# 12F1840_Controller_2020_03_04_A.net
KiCad netlist of a schematic drawn in EAGLE
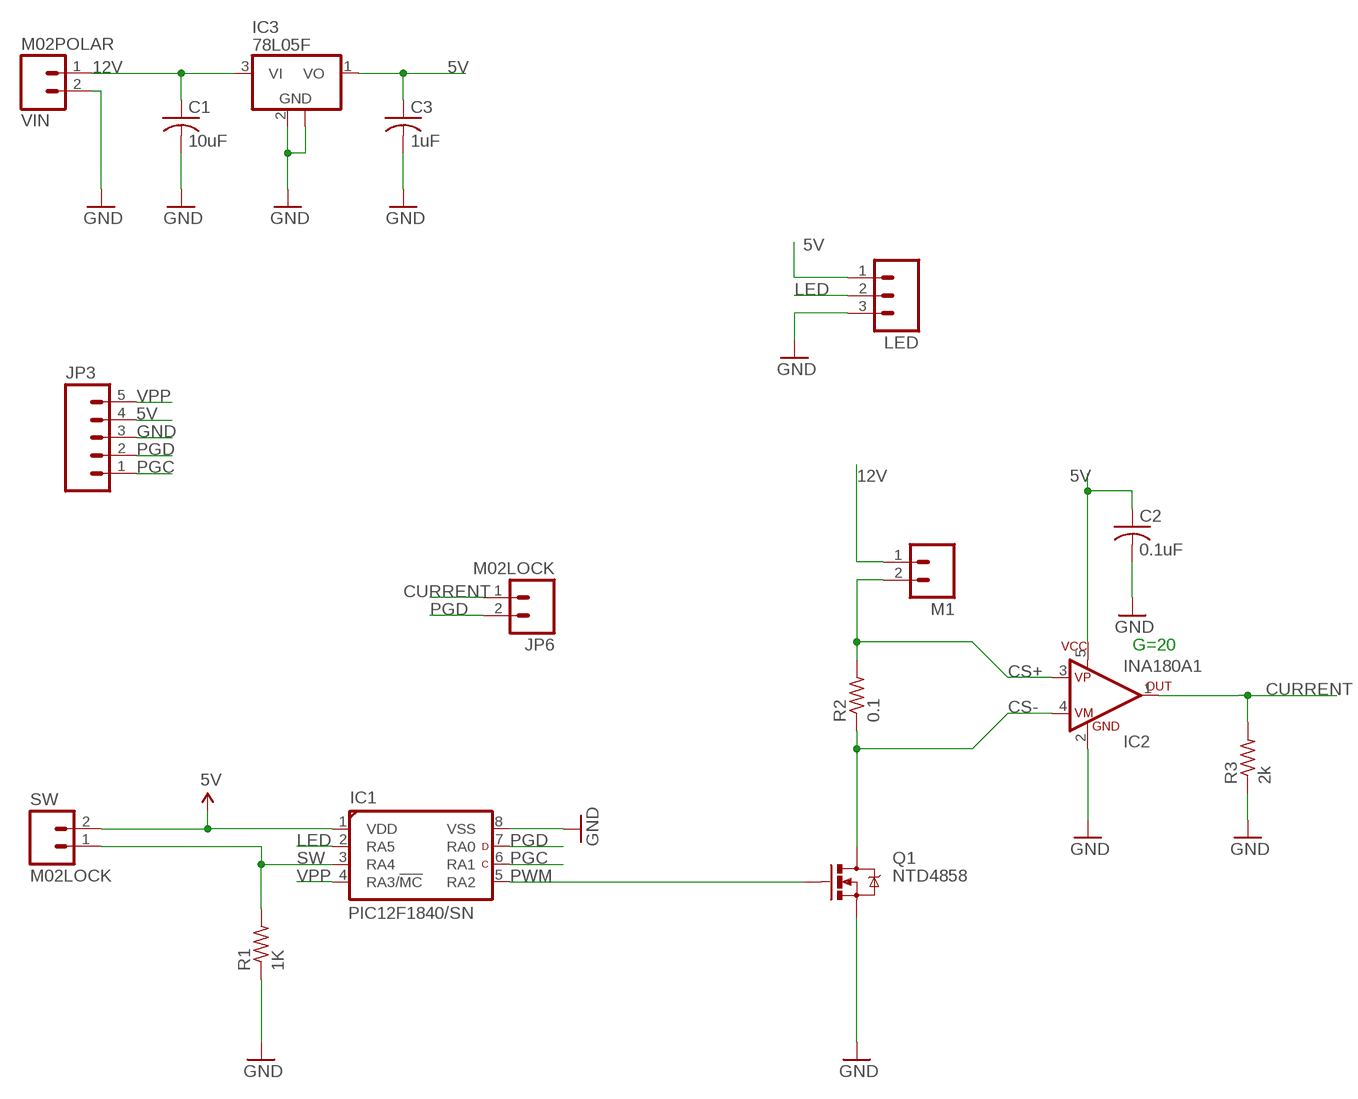
[diagram p0: schematic, sheet 1]

(export (version "E")
  (design (tool "Eeschema 10.0.6"))
  (components
    (comp (ref "C1")
      (value "10uF")
      (footprint "eagle-import:C1206")
      (libsource (lib "eagle-import") (part "C-USC1206"))
    )
    (comp (ref "C2")
      (value "0.1uF")
      (footprint "eagle-import:C1206")
      (libsource (lib "eagle-import") (part "C-USC1206"))
    )
    (comp (ref "C3")
      (value "1uF")
      (footprint "eagle-import:C1206")
      (libsource (lib "eagle-import") (part "C-USC1206"))
    )
    (comp (ref "IC1")
      (value "PIC12F1840/SN")
      (footprint "eagle-import:SOIC8-SN")
      (libsource (lib "eagle-import") (part "PIC12F1840/SN"))
    )
    (comp (ref "IC2")
      (value "INA180A1")
      (footprint "eagle-import:SOT23-5")
      (libsource (lib "eagle-import") (part "CS30"))
    )
    (comp (ref "IC3")
      (value "78L05F")
      (footprint "eagle-import:SOT89")
      (libsource (lib "eagle-import") (part "78LF05"))
    )
    (comp (ref "JP3")
      (value "M05LOCK")
      (footprint "eagle-import:1X05_LOCK")
      (libsource (lib "eagle-import") (part "M05LOCK"))
    )
    (comp (ref "JP6")
      (value "M02LOCK")
      (footprint "eagle-import:1X02_LOCK")
      (libsource (lib "eagle-import") (part "M02LOCK"))
    )
    (comp (ref "LED")
      (value "M03PTH")
      (footprint "eagle-import:1X03")
      (libsource (lib "eagle-import") (part "M03PTH"))
    )
    (comp (ref "M1")
      (value "M02POLAR")
      (footprint "eagle-import:MOLEX-1X2")
      (libsource (lib "eagle-import") (part "M02POLAR"))
    )
    (comp (ref "Q1")
      (value "NTD4858")
      (footprint "eagle-import:DPAK")
      (libsource (lib "eagle-import") (part "MOSFET-NCHANNELFDD8780"))
    )
    (comp (ref "R1")
      (value "1K")
      (footprint "eagle-import:R1206")
      (libsource (lib "eagle-import") (part "R-US_R1206"))
    )
    (comp (ref "R2")
      (value "0.1")
      (footprint "eagle-import:R2512")
      (libsource (lib "eagle-import") (part "R-US_R2512"))
    )
    (comp (ref "R3")
      (value "2k")
      (footprint "eagle-import:R1206")
      (libsource (lib "eagle-import") (part "R-US_R1206"))
    )
    (comp (ref "SW")
      (value "M02LOCK")
      (footprint "eagle-import:1X02_LOCK")
      (libsource (lib "eagle-import") (part "M02LOCK"))
    )
    (comp (ref "VIN")
      (value "M02POLAR")
      (footprint "eagle-import:MOLEX-1X2")
      (libsource (lib "eagle-import") (part "M02POLAR"))
    )
  )
  (nets
    (net (code "1") (name "/12V") (class "Default")
      (node (ref "C1") (pin "1") (pinfunction "1_1") (pintype "passive"))
      (node (ref "IC3") (pin "3") (pinfunction "VI_3") (pintype "input"))
      (node (ref "M1") (pin "1") (pinfunction "1_1") (pintype "passive"))
      (node (ref "VIN") (pin "1") (pinfunction "1_1") (pintype "passive"))
    )
    (net (code "2") (name "/CS+") (class "Default")
      (node (ref "IC2") (pin "3") (pinfunction "VP_3") (pintype "input"))
      (node (ref "M1") (pin "2") (pinfunction "2_2") (pintype "passive"))
      (node (ref "R2") (pin "2") (pinfunction "2_2") (pintype "passive"))
    )
    (net (code "3") (name "/CS-") (class "Default")
      (node (ref "IC2") (pin "4") (pinfunction "VM_4") (pintype "input"))
      (node (ref "Q1") (pin "4") (pinfunction "D_4") (pintype "passive"))
      (node (ref "R2") (pin "1") (pinfunction "1_1") (pintype "passive"))
    )
    (net (code "4") (name "/CURRENT") (class "Default")
      (node (ref "IC2") (pin "1") (pinfunction "OUT_1") (pintype "output"))
      (node (ref "JP6") (pin "1") (pinfunction "1_1") (pintype "passive"))
      (node (ref "R3") (pin "2") (pinfunction "2_2") (pintype "passive"))
    )
    (net (code "5") (name "/LED") (class "Default")
      (node (ref "IC1") (pin "2") (pinfunction "RA5_2") (pintype "bidirectional"))
      (node (ref "LED") (pin "2") (pinfunction "2_2") (pintype "passive"))
    )
    (net (code "6") (name "/PGC") (class "Default")
      (node (ref "IC1") (pin "6") (pinfunction "RA1_6") (pintype "bidirectional"))
      (node (ref "JP3") (pin "1") (pinfunction "1_1") (pintype "passive"))
    )
    (net (code "7") (name "/PGD") (class "Default")
      (node (ref "IC1") (pin "7") (pinfunction "RA0_7") (pintype "bidirectional"))
      (node (ref "JP3") (pin "2") (pinfunction "2_2") (pintype "passive"))
      (node (ref "JP6") (pin "2") (pinfunction "2_2") (pintype "passive"))
    )
    (net (code "8") (name "/PWM") (class "Default")
      (node (ref "IC1") (pin "5") (pinfunction "RA2_5") (pintype "bidirectional"))
      (node (ref "Q1") (pin "1") (pinfunction "G_1") (pintype "passive"))
    )
    (net (code "9") (name "/SW") (class "Default")
      (node (ref "IC1") (pin "3") (pinfunction "RA4_3") (pintype "bidirectional"))
      (node (ref "R1") (pin "2") (pinfunction "2_2") (pintype "passive"))
      (node (ref "SW") (pin "1") (pinfunction "1_1") (pintype "passive"))
    )
    (net (code "10") (name "/VPP") (class "Default")
      (node (ref "IC1") (pin "4") (pinfunction "RA3/~{MC}_4") (pintype "bidirectional"))
      (node (ref "JP3") (pin "5") (pinfunction "5_5") (pintype "passive"))
    )
    (net (code "11") (name "5V") (class "Default")
      (node (ref "C2") (pin "1") (pinfunction "1_1") (pintype "passive"))
      (node (ref "C3") (pin "1") (pinfunction "1_1") (pintype "passive"))
      (node (ref "IC1") (pin "1") (pinfunction "VDD_1") (pintype "passive"))
      (node (ref "IC2") (pin "5") (pinfunction "V+_5") (pintype "power_in"))
      (node (ref "IC3") (pin "1") (pinfunction "VO_1") (pintype "passive"))
      (node (ref "JP3") (pin "4") (pinfunction "4_4") (pintype "passive"))
      (node (ref "LED") (pin "1") (pinfunction "1_1") (pintype "passive"))
      (node (ref "SW") (pin "2") (pinfunction "2_2") (pintype "passive"))
    )
    (net (code "12") (name "GND") (class "Default")
      (node (ref "C1") (pin "2") (pinfunction "2_2") (pintype "passive"))
      (node (ref "C2") (pin "2") (pinfunction "2_2") (pintype "passive"))
      (node (ref "C3") (pin "2") (pinfunction "2_2") (pintype "passive"))
      (node (ref "IC1") (pin "8") (pinfunction "VSS_8") (pintype "passive"))
      (node (ref "IC2") (pin "2") (pinfunction "V-_2") (pintype "power_in"))
      (node (ref "IC3") (pin "2") (pinfunction "GND_2") (pintype "passive"))
      (node (ref "IC3") (pin "2@1") (pinfunction "GND_2@1") (pintype "passive"))
      (node (ref "JP3") (pin "3") (pinfunction "3_3") (pintype "passive"))
      (node (ref "LED") (pin "3") (pinfunction "3_3") (pintype "passive"))
      (node (ref "Q1") (pin "3") (pinfunction "S_3") (pintype "passive"))
      (node (ref "R1") (pin "1") (pinfunction "1_1") (pintype "passive"))
      (node (ref "R3") (pin "1") (pinfunction "1_1") (pintype "passive"))
      (node (ref "VIN") (pin "2") (pinfunction "2_2") (pintype "passive"))
    )
  )
)
